# 3_CPLD.net
KiCad netlist of a schematic drawn in Altium Designer
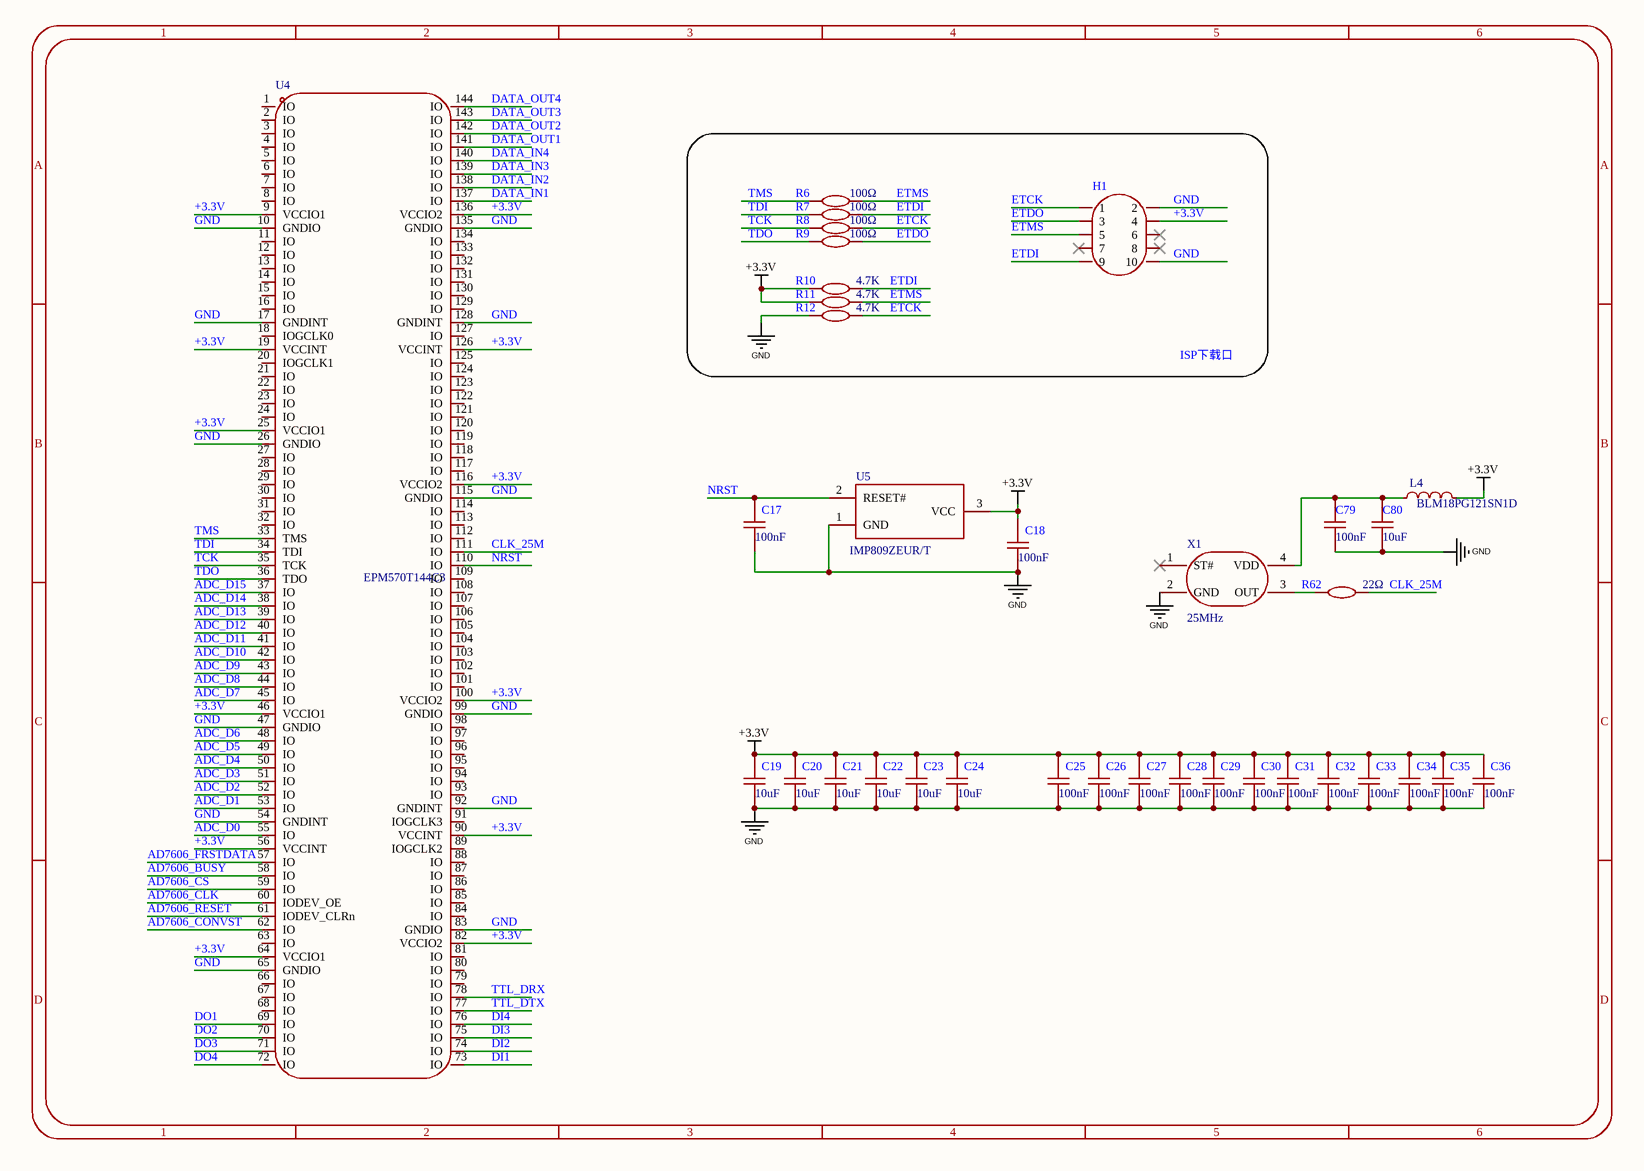
[diagram p0: 3_CPLD.schdoc]

(export (version "E")
  (design (tool "Eeschema 10.0.6"))
  (components
    (comp (ref "C17") (value "100nF") (footprint "C0603") (libsource (lib "34567890") (part "CAP_0603")))
    (comp (ref "C18") (value "100nF") (footprint "C0603") (libsource (lib "34567890") (part "CAP_0603")))
    (comp (ref "C19") (value "10uF") (footprint "C0805") (libsource (lib "34567890") (part "CAP_0805")))
    (comp (ref "C20") (value "10uF") (footprint "C0805") (libsource (lib "34567890") (part "CAP_0805")))
    (comp (ref "C21") (value "10uF") (footprint "C0805") (libsource (lib "34567890") (part "CAP_0805")))
    (comp (ref "C22") (value "10uF") (footprint "C0805") (libsource (lib "34567890") (part "CAP_0805")))
    (comp (ref "C23") (value "10uF") (footprint "C0805") (libsource (lib "34567890") (part "CAP_0805")))
    (comp (ref "C24") (value "10uF") (footprint "C0805") (libsource (lib "34567890") (part "CAP_0805")))
    (comp (ref "C25") (value "100nF") (footprint "C0603") (libsource (lib "34567890") (part "CAP_0603")))
    (comp (ref "C26") (value "100nF") (footprint "C0603") (libsource (lib "34567890") (part "CAP_0603")))
    (comp (ref "C27") (value "100nF") (footprint "C0603") (libsource (lib "34567890") (part "CAP_0603")))
    (comp (ref "C28") (value "100nF") (footprint "C0603") (libsource (lib "34567890") (part "CAP_0603")))
    (comp (ref "C29") (value "100nF") (footprint "C0603") (libsource (lib "34567890") (part "CAP_0603")))
    (comp (ref "C30") (value "100nF") (footprint "C0603") (libsource (lib "34567890") (part "CAP_0603")))
    (comp (ref "C31") (value "100nF") (footprint "C0603") (libsource (lib "34567890") (part "CAP_0603")))
    (comp (ref "C32") (value "100nF") (footprint "C0603") (libsource (lib "34567890") (part "CAP_0603")))
    (comp (ref "C33") (value "100nF") (footprint "C0603") (libsource (lib "34567890") (part "CAP_0603")))
    (comp (ref "C34") (value "100nF") (footprint "C0603") (libsource (lib "34567890") (part "CAP_0603")))
    (comp (ref "C35") (value "100nF") (footprint "C0603") (libsource (lib "34567890") (part "CAP_0603")))
    (comp (ref "C36") (value "100nF") (footprint "C0603") (libsource (lib "34567890") (part "CAP_0603")))
    (comp (ref "C79") (value "100nF") (footprint "C0603") (libsource (lib "34567890") (part "CAP_0603")))
    (comp (ref "C80") (value "10uF") (footprint "C0805") (libsource (lib "34567890") (part "CAP_0805")))
    (comp (ref "H1")
      (value "~")
      (footprint "HDR-TH_10P-P2.54-V-F-R2-C5-S2.54")
      (libsource (lib "34567890") (part "HDR-F_2.54_2x5"))
    )
    (comp (ref "L4")
      (value "BLM18PG121SN1D")
      (footprint "L0603")
      (libsource (lib "34567890") (part "BLM18PG121SN1D"))
    )
    (comp (ref "R6") (value "100Ω") (footprint "R0603") (libsource (lib "34567890") (part "Res_0603")))
    (comp (ref "R7") (value "100Ω") (footprint "R0603") (libsource (lib "34567890") (part "Res_0603")))
    (comp (ref "R8") (value "100Ω") (footprint "R0603") (libsource (lib "34567890") (part "Res_0603")))
    (comp (ref "R9") (value "100Ω") (footprint "R0603") (libsource (lib "34567890") (part "Res_0603")))
    (comp (ref "R10") (value "4.7K") (footprint "R0603") (libsource (lib "34567890") (part "Res_0603")))
    (comp (ref "R11") (value "4.7K") (footprint "R0603") (libsource (lib "34567890") (part "Res_0603")))
    (comp (ref "R12") (value "4.7K") (footprint "R0603") (libsource (lib "34567890") (part "Res_0603")))
    (comp (ref "R62") (value "22Ω") (footprint "R0603") (libsource (lib "34567890") (part "Res_0603")))
    (comp (ref "U4")
      (value "EPM570T144C3")
      (footprint "TQFP-144_L20.0-W20.0-P0.50-LS22.0-BL")
      (libsource (lib "34567890") (part "EPM570T144C3"))
    )
    (comp (ref "U5")
      (value "IMP809ZEUR/T")
      (footprint "SOT-23-3_L2.9-W1.6-P1.90-LS2.8-BR")
      (libsource (lib "34567890") (part "IMP809ZEUR/T"))
    )
    (comp (ref "X1")
      (value "25MHz")
      (footprint "OSC-SMD_4P-L2.5-W2.0-BL")
      (libsource (lib "34567890") (part "X1G0041710033"))
    )
  )
  (nets
    (net (code "1") (name "+3.3V") (class "Default")
      (node (ref "C18") (pin "2") (pinfunction "2_2") (pintype "passive"))
      (node (ref "C19") (pin "2") (pinfunction "2_2") (pintype "passive"))
      (node (ref "C20") (pin "2") (pinfunction "2_2") (pintype "passive"))
      (node (ref "C21") (pin "2") (pinfunction "2_2") (pintype "passive"))
      (node (ref "C22") (pin "2") (pinfunction "2_2") (pintype "passive"))
      (node (ref "C23") (pin "2") (pinfunction "2_2") (pintype "passive"))
      (node (ref "C24") (pin "2") (pinfunction "2_2") (pintype "passive"))
      (node (ref "C25") (pin "2") (pinfunction "2_2") (pintype "passive"))
      (node (ref "C26") (pin "2") (pinfunction "2_2") (pintype "passive"))
      (node (ref "C27") (pin "2") (pinfunction "2_2") (pintype "passive"))
      (node (ref "C28") (pin "2") (pinfunction "2_2") (pintype "passive"))
      (node (ref "C29") (pin "2") (pinfunction "2_2") (pintype "passive"))
      (node (ref "C30") (pin "2") (pinfunction "2_2") (pintype "passive"))
      (node (ref "C31") (pin "2") (pinfunction "2_2") (pintype "passive"))
      (node (ref "C32") (pin "2") (pinfunction "2_2") (pintype "passive"))
      (node (ref "C33") (pin "2") (pinfunction "2_2") (pintype "passive"))
      (node (ref "C34") (pin "2") (pinfunction "2_2") (pintype "passive"))
      (node (ref "C35") (pin "2") (pinfunction "2_2") (pintype "passive"))
      (node (ref "C36") (pin "2") (pinfunction "2_2") (pintype "passive"))
      (node (ref "H1") (pin "4") (pinfunction "4_4") (pintype "passive"))
      (node (ref "L4") (pin "2") (pinfunction "2_2") (pintype "passive"))
      (node (ref "R10") (pin "1") (pinfunction "1_1") (pintype "passive"))
      (node (ref "R11") (pin "1") (pinfunction "1_1") (pintype "passive"))
      (node (ref "U4") (pin "100") (pinfunction "VCCIO2_100") (pintype "passive"))
      (node (ref "U4") (pin "116") (pinfunction "VCCIO2_116") (pintype "passive"))
      (node (ref "U4") (pin "126") (pinfunction "VCCINT_126") (pintype "passive"))
      (node (ref "U4") (pin "136") (pinfunction "VCCIO2_136") (pintype "passive"))
      (node (ref "U4") (pin "19") (pinfunction "VCCINT_19") (pintype "passive"))
      (node (ref "U4") (pin "25") (pinfunction "VCCIO1_25") (pintype "passive"))
      (node (ref "U4") (pin "46") (pinfunction "VCCIO1_46") (pintype "passive"))
      (node (ref "U4") (pin "56") (pinfunction "VCCINT_56") (pintype "passive"))
      (node (ref "U4") (pin "64") (pinfunction "VCCIO1_64") (pintype "passive"))
      (node (ref "U4") (pin "82") (pinfunction "VCCIO2_82") (pintype "passive"))
      (node (ref "U4") (pin "9") (pinfunction "VCCIO1_9") (pintype "passive"))
      (node (ref "U4") (pin "90") (pinfunction "VCCINT_90") (pintype "passive"))
      (node (ref "U5") (pin "3") (pinfunction "VCC_3") (pintype "passive"))
    )
    (net (code "2") (name "/AD7606_BUSY") (class "Default")
      (node (ref "U4") (pin "58") (pinfunction "IO_58") (pintype "passive"))
    )
    (net (code "3") (name "/AD7606_CLK") (class "Default")
      (node (ref "U4") (pin "60") (pinfunction "IODEV_OE_60") (pintype "passive"))
    )
    (net (code "4") (name "/AD7606_CONVST") (class "Default")
      (node (ref "U4") (pin "62") (pinfunction "IO_62") (pintype "passive"))
    )
    (net (code "5") (name "/AD7606_CS") (class "Default")
      (node (ref "U4") (pin "59") (pinfunction "IO_59") (pintype "passive"))
    )
    (net (code "6") (name "/AD7606_FRSTDATA") (class "Default")
      (node (ref "U4") (pin "57") (pinfunction "IO_57") (pintype "passive"))
    )
    (net (code "7") (name "/AD7606_RESET") (class "Default")
      (node (ref "U4") (pin "61") (pinfunction "IODEV_CLRn_61") (pintype "passive"))
    )
    (net (code "8") (name "/ADC_D0") (class "Default")
      (node (ref "U4") (pin "55") (pinfunction "IO_55") (pintype "passive"))
    )
    (net (code "9") (name "/ADC_D1") (class "Default")
      (node (ref "U4") (pin "53") (pinfunction "IO_53") (pintype "passive"))
    )
    (net (code "10") (name "/ADC_D2") (class "Default")
      (node (ref "U4") (pin "52") (pinfunction "IO_52") (pintype "passive"))
    )
    (net (code "11") (name "/ADC_D3") (class "Default")
      (node (ref "U4") (pin "51") (pinfunction "IO_51") (pintype "passive"))
    )
    (net (code "12") (name "/ADC_D4") (class "Default")
      (node (ref "U4") (pin "50") (pinfunction "IO_50") (pintype "passive"))
    )
    (net (code "13") (name "/ADC_D5") (class "Default")
      (node (ref "U4") (pin "49") (pinfunction "IO_49") (pintype "passive"))
    )
    (net (code "14") (name "/ADC_D6") (class "Default")
      (node (ref "U4") (pin "48") (pinfunction "IO_48") (pintype "passive"))
    )
    (net (code "15") (name "/ADC_D7") (class "Default")
      (node (ref "U4") (pin "45") (pinfunction "IO_45") (pintype "passive"))
    )
    (net (code "16") (name "/ADC_D8") (class "Default")
      (node (ref "U4") (pin "44") (pinfunction "IO_44") (pintype "passive"))
    )
    (net (code "17") (name "/ADC_D9") (class "Default")
      (node (ref "U4") (pin "43") (pinfunction "IO_43") (pintype "passive"))
    )
    (net (code "18") (name "/ADC_D10") (class "Default")
      (node (ref "U4") (pin "42") (pinfunction "IO_42") (pintype "passive"))
    )
    (net (code "19") (name "/ADC_D11") (class "Default")
      (node (ref "U4") (pin "41") (pinfunction "IO_41") (pintype "passive"))
    )
    (net (code "20") (name "/ADC_D12") (class "Default")
      (node (ref "U4") (pin "40") (pinfunction "IO_40") (pintype "passive"))
    )
    (net (code "21") (name "/ADC_D13") (class "Default")
      (node (ref "U4") (pin "39") (pinfunction "IO_39") (pintype "passive"))
    )
    (net (code "22") (name "/ADC_D14") (class "Default")
      (node (ref "U4") (pin "38") (pinfunction "IO_38") (pintype "passive"))
    )
    (net (code "23") (name "/ADC_D15") (class "Default")
      (node (ref "U4") (pin "37") (pinfunction "IO_37") (pintype "passive"))
    )
    (net (code "24") (name "/CLK_25M") (class "Default")
      (node (ref "R62") (pin "2") (pinfunction "2_2") (pintype "passive"))
      (node (ref "U4") (pin "111") (pinfunction "IO_111") (pintype "passive"))
    )
    (net (code "25") (name "/DATA_IN1") (class "Default")
      (node (ref "U4") (pin "137") (pinfunction "IO_137") (pintype "passive"))
    )
    (net (code "26") (name "/DATA_IN2") (class "Default")
      (node (ref "U4") (pin "138") (pinfunction "IO_138") (pintype "passive"))
    )
    (net (code "27") (name "/DATA_IN3") (class "Default")
      (node (ref "U4") (pin "139") (pinfunction "IO_139") (pintype "passive"))
    )
    (net (code "28") (name "/DATA_IN4") (class "Default")
      (node (ref "U4") (pin "140") (pinfunction "IO_140") (pintype "passive"))
    )
    (net (code "29") (name "/DATA_OUT1") (class "Default")
      (node (ref "U4") (pin "141") (pinfunction "IO_141") (pintype "passive"))
    )
    (net (code "30") (name "/DATA_OUT2") (class "Default")
      (node (ref "U4") (pin "142") (pinfunction "IO_142") (pintype "passive"))
    )
    (net (code "31") (name "/DATA_OUT3") (class "Default")
      (node (ref "U4") (pin "143") (pinfunction "IO_143") (pintype "passive"))
    )
    (net (code "32") (name "/DATA_OUT4") (class "Default")
      (node (ref "U4") (pin "144") (pinfunction "IO_144") (pintype "passive"))
    )
    (net (code "33") (name "/DI1") (class "Default")
      (node (ref "U4") (pin "73") (pinfunction "IO_73") (pintype "passive"))
    )
    (net (code "34") (name "/DI2") (class "Default")
      (node (ref "U4") (pin "74") (pinfunction "IO_74") (pintype "passive"))
    )
    (net (code "35") (name "/DI3") (class "Default")
      (node (ref "U4") (pin "75") (pinfunction "IO_75") (pintype "passive"))
    )
    (net (code "36") (name "/DI4") (class "Default")
      (node (ref "U4") (pin "76") (pinfunction "IO_76") (pintype "passive"))
    )
    (net (code "37") (name "/DO1") (class "Default")
      (node (ref "U4") (pin "69") (pinfunction "IO_69") (pintype "passive"))
    )
    (net (code "38") (name "/DO2") (class "Default")
      (node (ref "U4") (pin "70") (pinfunction "IO_70") (pintype "passive"))
    )
    (net (code "39") (name "/DO3") (class "Default")
      (node (ref "U4") (pin "71") (pinfunction "IO_71") (pintype "passive"))
    )
    (net (code "40") (name "/DO4") (class "Default")
      (node (ref "U4") (pin "72") (pinfunction "IO_72") (pintype "passive"))
    )
    (net (code "41") (name "/ETCK") (class "Default")
      (node (ref "H1") (pin "1") (pinfunction "1_1") (pintype "passive"))
      (node (ref "R12") (pin "2") (pinfunction "2_2") (pintype "passive"))
      (node (ref "R8") (pin "2") (pinfunction "2_2") (pintype "passive"))
    )
    (net (code "42") (name "/ETDI") (class "Default")
      (node (ref "H1") (pin "9") (pinfunction "9_9") (pintype "passive"))
      (node (ref "R10") (pin "2") (pinfunction "2_2") (pintype "passive"))
      (node (ref "R7") (pin "2") (pinfunction "2_2") (pintype "passive"))
    )
    (net (code "43") (name "/ETDO") (class "Default")
      (node (ref "H1") (pin "3") (pinfunction "3_3") (pintype "passive"))
      (node (ref "R9") (pin "2") (pinfunction "2_2") (pintype "passive"))
    )
    (net (code "44") (name "/ETMS") (class "Default")
      (node (ref "H1") (pin "5") (pinfunction "5_5") (pintype "passive"))
      (node (ref "R11") (pin "2") (pinfunction "2_2") (pintype "passive"))
      (node (ref "R6") (pin "2") (pinfunction "2_2") (pintype "passive"))
    )
    (net (code "45") (name "/NRST") (class "Default")
      (node (ref "C17") (pin "2") (pinfunction "2_2") (pintype "passive"))
      (node (ref "U4") (pin "110") (pinfunction "IO_110") (pintype "passive"))
      (node (ref "U5") (pin "2") (pinfunction "RESET#_2") (pintype "passive"))
    )
    (net (code "46") (name "/TCK") (class "Default")
      (node (ref "R8") (pin "1") (pinfunction "1_1") (pintype "passive"))
      (node (ref "U4") (pin "35") (pinfunction "TCK_35") (pintype "passive"))
    )
    (net (code "47") (name "/TDI") (class "Default")
      (node (ref "R7") (pin "1") (pinfunction "1_1") (pintype "passive"))
      (node (ref "U4") (pin "34") (pinfunction "TDI_34") (pintype "passive"))
    )
    (net (code "48") (name "/TDO") (class "Default")
      (node (ref "R9") (pin "1") (pinfunction "1_1") (pintype "passive"))
      (node (ref "U4") (pin "36") (pinfunction "TDO_36") (pintype "passive"))
    )
    (net (code "49") (name "/TMS") (class "Default")
      (node (ref "R6") (pin "1") (pinfunction "1_1") (pintype "passive"))
      (node (ref "U4") (pin "33") (pinfunction "TMS_33") (pintype "passive"))
    )
    (net (code "50") (name "/TTL_DRX") (class "Default")
      (node (ref "U4") (pin "78") (pinfunction "IO_78") (pintype "passive"))
    )
    (net (code "51") (name "/TTL_DTX") (class "Default")
      (node (ref "U4") (pin "77") (pinfunction "IO_77") (pintype "passive"))
    )
    (net (code "52") (name "GND") (class "Default")
      (node (ref "C17") (pin "1") (pinfunction "1_1") (pintype "passive"))
      (node (ref "C18") (pin "1") (pinfunction "1_1") (pintype "passive"))
      (node (ref "C19") (pin "1") (pinfunction "1_1") (pintype "passive"))
      (node (ref "C20") (pin "1") (pinfunction "1_1") (pintype "passive"))
      (node (ref "C21") (pin "1") (pinfunction "1_1") (pintype "passive"))
      (node (ref "C22") (pin "1") (pinfunction "1_1") (pintype "passive"))
      (node (ref "C23") (pin "1") (pinfunction "1_1") (pintype "passive"))
      (node (ref "C24") (pin "1") (pinfunction "1_1") (pintype "passive"))
      (node (ref "C25") (pin "1") (pinfunction "1_1") (pintype "passive"))
      (node (ref "C26") (pin "1") (pinfunction "1_1") (pintype "passive"))
      (node (ref "C27") (pin "1") (pinfunction "1_1") (pintype "passive"))
      (node (ref "C28") (pin "1") (pinfunction "1_1") (pintype "passive"))
      (node (ref "C29") (pin "1") (pinfunction "1_1") (pintype "passive"))
      (node (ref "C30") (pin "1") (pinfunction "1_1") (pintype "passive"))
      (node (ref "C31") (pin "1") (pinfunction "1_1") (pintype "passive"))
      (node (ref "C32") (pin "1") (pinfunction "1_1") (pintype "passive"))
      (node (ref "C33") (pin "1") (pinfunction "1_1") (pintype "passive"))
      (node (ref "C34") (pin "1") (pinfunction "1_1") (pintype "passive"))
      (node (ref "C35") (pin "1") (pinfunction "1_1") (pintype "passive"))
      (node (ref "C36") (pin "1") (pinfunction "1_1") (pintype "passive"))
      (node (ref "C79") (pin "2") (pinfunction "2_2") (pintype "passive"))
      (node (ref "C80") (pin "1") (pinfunction "1_1") (pintype "passive"))
      (node (ref "H1") (pin "10") (pinfunction "10_10") (pintype "passive"))
      (node (ref "H1") (pin "2") (pinfunction "2_2") (pintype "passive"))
      (node (ref "R12") (pin "1") (pinfunction "1_1") (pintype "passive"))
      (node (ref "U4") (pin "10") (pinfunction "GNDIO_10") (pintype "passive"))
      (node (ref "U4") (pin "115") (pinfunction "GNDIO_115") (pintype "passive"))
      (node (ref "U4") (pin "128") (pinfunction "GNDINT_128") (pintype "passive"))
      (node (ref "U4") (pin "135") (pinfunction "GNDIO_135") (pintype "passive"))
      (node (ref "U4") (pin "17") (pinfunction "GNDINT_17") (pintype "passive"))
      (node (ref "U4") (pin "26") (pinfunction "GNDIO_26") (pintype "passive"))
      (node (ref "U4") (pin "47") (pinfunction "GNDIO_47") (pintype "passive"))
      (node (ref "U4") (pin "54") (pinfunction "GNDINT_54") (pintype "passive"))
      (node (ref "U4") (pin "65") (pinfunction "GNDIO_65") (pintype "passive"))
      (node (ref "U4") (pin "83") (pinfunction "GNDIO_83") (pintype "passive"))
      (node (ref "U4") (pin "92") (pinfunction "GNDINT_92") (pintype "passive"))
      (node (ref "U4") (pin "99") (pinfunction "GNDIO_99") (pintype "passive"))
      (node (ref "U5") (pin "1") (pinfunction "GND_1") (pintype "passive"))
      (node (ref "X1") (pin "2") (pinfunction "GND_2") (pintype "passive"))
    )
    (net (code "53") (name "Net-(X1-OUT)") (class "Default")
      (node (ref "R62") (pin "1") (pinfunction "1_1") (pintype "passive"))
      (node (ref "X1") (pin "3") (pinfunction "OUT_3") (pintype "passive"))
    )
    (net (code "54") (name "Net-(X1-VDD)") (class "Default")
      (node (ref "C79") (pin "1") (pinfunction "1_1") (pintype "passive"))
      (node (ref "C80") (pin "2") (pinfunction "2_2") (pintype "passive"))
      (node (ref "L4") (pin "1") (pinfunction "1_1") (pintype "passive"))
      (node (ref "X1") (pin "4") (pinfunction "VDD_4") (pintype "passive"))
    )
    (net (code "55") (name "unconnected-(H1-Pad6)") (class "Default")
      (node (ref "H1") (pin "6") (pinfunction "6_6") (pintype "passive+no_connect"))
    )
    (net (code "56") (name "unconnected-(H1-Pad7)") (class "Default")
      (node (ref "H1") (pin "7") (pinfunction "7_7") (pintype "passive+no_connect"))
    )
    (net (code "57") (name "unconnected-(H1-Pad8)") (class "Default")
      (node (ref "H1") (pin "8") (pinfunction "8_8") (pintype "passive+no_connect"))
    )
    (net (code "58") (name "unconnected-(U4-IO-Pad1)") (class "Default")
      (node (ref "U4") (pin "1") (pinfunction "IO_1") (pintype "passive"))
    )
    (net (code "59") (name "unconnected-(U4-IO-Pad2)") (class "Default")
      (node (ref "U4") (pin "2") (pinfunction "IO_2") (pintype "passive"))
    )
    (net (code "60") (name "unconnected-(U4-IO-Pad3)") (class "Default")
      (node (ref "U4") (pin "3") (pinfunction "IO_3") (pintype "passive"))
    )
    (net (code "61") (name "unconnected-(U4-IO-Pad4)") (class "Default")
      (node (ref "U4") (pin "4") (pinfunction "IO_4") (pintype "passive"))
    )
    (net (code "62") (name "unconnected-(U4-IO-Pad5)") (class "Default")
      (node (ref "U4") (pin "5") (pinfunction "IO_5") (pintype "passive"))
    )
    (net (code "63") (name "unconnected-(U4-IO-Pad6)") (class "Default")
      (node (ref "U4") (pin "6") (pinfunction "IO_6") (pintype "passive"))
    )
    (net (code "64") (name "unconnected-(U4-IO-Pad7)") (class "Default")
      (node (ref "U4") (pin "7") (pinfunction "IO_7") (pintype "passive"))
    )
    (net (code "65") (name "unconnected-(U4-IO-Pad8)") (class "Default")
      (node (ref "U4") (pin "8") (pinfunction "IO_8") (pintype "passive"))
    )
    (net (code "66") (name "unconnected-(U4-IO-Pad11)") (class "Default")
      (node (ref "U4") (pin "11") (pinfunction "IO_11") (pintype "passive"))
    )
    (net (code "67") (name "unconnected-(U4-IO-Pad12)") (class "Default")
      (node (ref "U4") (pin "12") (pinfunction "IO_12") (pintype "passive"))
    )
    (net (code "68") (name "unconnected-(U4-IO-Pad13)") (class "Default")
      (node (ref "U4") (pin "13") (pinfunction "IO_13") (pintype "passive"))
    )
    (net (code "69") (name "unconnected-(U4-IO-Pad14)") (class "Default")
      (node (ref "U4") (pin "14") (pinfunction "IO_14") (pintype "passive"))
    )
    (net (code "70") (name "unconnected-(U4-IO-Pad15)") (class "Default")
      (node (ref "U4") (pin "15") (pinfunction "IO_15") (pintype "passive"))
    )
    (net (code "71") (name "unconnected-(U4-IO-Pad16)") (class "Default")
      (node (ref "U4") (pin "16") (pinfunction "IO_16") (pintype "passive"))
    )
    (net (code "72") (name "unconnected-(U4-IO-Pad21)") (class "Default")
      (node (ref "U4") (pin "21") (pinfunction "IO_21") (pintype "passive"))
    )
    (net (code "73") (name "unconnected-(U4-IO-Pad22)") (class "Default")
      (node (ref "U4") (pin "22") (pinfunction "IO_22") (pintype "passive"))
    )
    (net (code "74") (name "unconnected-(U4-IO-Pad23)") (class "Default")
      (node (ref "U4") (pin "23") (pinfunction "IO_23") (pintype "passive"))
    )
    (net (code "75") (name "unconnected-(U4-IO-Pad24)") (class "Default")
      (node (ref "U4") (pin "24") (pinfunction "IO_24") (pintype "passive"))
    )
    (net (code "76") (name "unconnected-(U4-IO-Pad27)") (class "Default")
      (node (ref "U4") (pin "27") (pinfunction "IO_27") (pintype "passive"))
    )
    (net (code "77") (name "unconnected-(U4-IO-Pad28)") (class "Default")
      (node (ref "U4") (pin "28") (pinfunction "IO_28") (pintype "passive"))
    )
    (net (code "78") (name "unconnected-(U4-IO-Pad29)") (class "Default")
      (node (ref "U4") (pin "29") (pinfunction "IO_29") (pintype "passive"))
    )
    (net (code "79") (name "unconnected-(U4-IO-Pad30)") (class "Default")
      (node (ref "U4") (pin "30") (pinfunction "IO_30") (pintype "passive"))
    )
    (net (code "80") (name "unconnected-(U4-IO-Pad31)") (class "Default")
      (node (ref "U4") (pin "31") (pinfunction "IO_31") (pintype "passive"))
    )
    (net (code "81") (name "unconnected-(U4-IO-Pad32)") (class "Default")
      (node (ref "U4") (pin "32") (pinfunction "IO_32") (pintype "passive"))
    )
    (net (code "82") (name "unconnected-(U4-IO-Pad63)") (class "Default")
      (node (ref "U4") (pin "63") (pinfunction "IO_63") (pintype "passive"))
    )
    (net (code "83") (name "unconnected-(U4-IO-Pad66)") (class "Default")
      (node (ref "U4") (pin "66") (pinfunction "IO_66") (pintype "passive"))
    )
    (net (code "84") (name "unconnected-(U4-IO-Pad67)") (class "Default")
      (node (ref "U4") (pin "67") (pinfunction "IO_67") (pintype "passive"))
    )
    (net (code "85") (name "unconnected-(U4-IO-Pad68)") (class "Default")
      (node (ref "U4") (pin "68") (pinfunction "IO_68") (pintype "passive"))
    )
    (net (code "86") (name "unconnected-(U4-IO-Pad79)") (class "Default")
      (node (ref "U4") (pin "79") (pinfunction "IO_79") (pintype "passive"))
    )
    (net (code "87") (name "unconnected-(U4-IO-Pad80)") (class "Default")
      (node (ref "U4") (pin "80") (pinfunction "IO_80") (pintype "passive"))
    )
    (net (code "88") (name "unconnected-(U4-IO-Pad81)") (class "Default")
      (node (ref "U4") (pin "81") (pinfunction "IO_81") (pintype "passive"))
    )
    (net (code "89") (name "unconnected-(U4-IO-Pad84)") (class "Default")
      (node (ref "U4") (pin "84") (pinfunction "IO_84") (pintype "passive"))
    )
    (net (code "90") (name "unconnected-(U4-IO-Pad85)") (class "Default")
      (node (ref "U4") (pin "85") (pinfunction "IO_85") (pintype "passive"))
    )
    (net (code "91") (name "unconnected-(U4-IO-Pad86)") (class "Default")
      (node (ref "U4") (pin "86") (pinfunction "IO_86") (pintype "passive"))
    )
    (net (code "92") (name "unconnected-(U4-IO-Pad87)") (class "Default")
      (node (ref "U4") (pin "87") (pinfunction "IO_87") (pintype "passive"))
    )
    (net (code "93") (name "unconnected-(U4-IO-Pad88)") (class "Default")
      (node (ref "U4") (pin "88") (pinfunction "IO_88") (pintype "passive"))
    )
    (net (code "94") (name "unconnected-(U4-IO-Pad93)") (class "Default")
      (node (ref "U4") (pin "93") (pinfunction "IO_93") (pintype "passive"))
    )
    (net (code "95") (name "unconnected-(U4-IO-Pad94)") (class "Default")
      (node (ref "U4") (pin "94") (pinfunction "IO_94") (pintype "passive"))
    )
    (net (code "96") (name "unconnected-(U4-IO-Pad95)") (class "Default")
      (node (ref "U4") (pin "95") (pinfunction "IO_95") (pintype "passive"))
    )
    (net (code "97") (name "unconnected-(U4-IO-Pad96)") (class "Default")
      (node (ref "U4") (pin "96") (pinfunction "IO_96") (pintype "passive"))
    )
    (net (code "98") (name "unconnected-(U4-IO-Pad97)") (class "Default")
      (node (ref "U4") (pin "97") (pinfunction "IO_97") (pintype "passive"))
    )
    (net (code "99") (name "unconnected-(U4-IO-Pad98)") (class "Default")
      (node (ref "U4") (pin "98") (pinfunction "IO_98") (pintype "passive"))
    )
    (net (code "100") (name "unconnected-(U4-IO-Pad101)") (class "Default")
      (node (ref "U4") (pin "101") (pinfunction "IO_101") (pintype "passive"))
    )
    (net (code "101") (name "unconnected-(U4-IO-Pad102)") (class "Default")
      (node (ref "U4") (pin "102") (pinfunction "IO_102") (pintype "passive"))
    )
    (net (code "102") (name "unconnected-(U4-IO-Pad103)") (class "Default")
      (node (ref "U4") (pin "103") (pinfunction "IO_103") (pintype "passive"))
    )
    (net (code "103") (name "unconnected-(U4-IO-Pad104)") (class "Default")
      (node (ref "U4") (pin "104") (pinfunction "IO_104") (pintype "passive"))
    )
    (net (code "104") (name "unconnected-(U4-IO-Pad105)") (class "Default")
      (node (ref "U4") (pin "105") (pinfunction "IO_105") (pintype "passive"))
    )
    (net (code "105") (name "unconnected-(U4-IO-Pad106)") (class "Default")
      (node (ref "U4") (pin "106") (pinfunction "IO_106") (pintype "passive"))
    )
    (net (code "106") (name "unconnected-(U4-IO-Pad107)") (class "Default")
      (node (ref "U4") (pin "107") (pinfunction "IO_107") (pintype "passive"))
    )
    (net (code "107") (name "unconnected-(U4-IO-Pad108)") (class "Default")
      (node (ref "U4") (pin "108") (pinfunction "IO_108") (pintype "passive"))
    )
    (net (code "108") (name "unconnected-(U4-IO-Pad109)") (class "Default")
      (node (ref "U4") (pin "109") (pinfunction "IO_109") (pintype "passive"))
    )
    (net (code "109") (name "unconnected-(U4-IO-Pad112)") (class "Default")
      (node (ref "U4") (pin "112") (pinfunction "IO_112") (pintype "passive"))
    )
    (net (code "110") (name "unconnected-(U4-IO-Pad113)") (class "Default")
      (node (ref "U4") (pin "113") (pinfunction "IO_113") (pintype "passive"))
    )
    (net (code "111") (name "unconnected-(U4-IO-Pad114)") (class "Default")
      (node (ref "U4") (pin "114") (pinfunction "IO_114") (pintype "passive"))
    )
    (net (code "112") (name "unconnected-(U4-IO-Pad117)") (class "Default")
      (node (ref "U4") (pin "117") (pinfunction "IO_117") (pintype "passive"))
    )
    (net (code "113") (name "unconnected-(U4-IO-Pad118)") (class "Default")
      (node (ref "U4") (pin "118") (pinfunction "IO_118") (pintype "passive"))
    )
    (net (code "114") (name "unconnected-(U4-IO-Pad119)") (class "Default")
      (node (ref "U4") (pin "119") (pinfunction "IO_119") (pintype "passive"))
    )
    (net (code "115") (name "unconnected-(U4-IO-Pad120)") (class "Default")
      (node (ref "U4") (pin "120") (pinfunction "IO_120") (pintype "passive"))
    )
    (net (code "116") (name "unconnected-(U4-IO-Pad121)") (class "Default")
      (node (ref "U4") (pin "121") (pinfunction "IO_121") (pintype "passive"))
    )
    (net (code "117") (name "unconnected-(U4-IO-Pad122)") (class "Default")
      (node (ref "U4") (pin "122") (pinfunction "IO_122") (pintype "passive"))
    )
    (net (code "118") (name "unconnected-(U4-IO-Pad123)") (class "Default")
      (node (ref "U4") (pin "123") (pinfunction "IO_123") (pintype "passive"))
    )
    (net (code "119") (name "unconnected-(U4-IO-Pad124)") (class "Default")
      (node (ref "U4") (pin "124") (pinfunction "IO_124") (pintype "passive"))
    )
    (net (code "120") (name "unconnected-(U4-IO-Pad125)") (class "Default")
      (node (ref "U4") (pin "125") (pinfunction "IO_125") (pintype "passive"))
    )
    (net (code "121") (name "unconnected-(U4-IO-Pad127)") (class "Default")
      (node (ref "U4") (pin "127") (pinfunction "IO_127") (pintype "passive"))
    )
    (net (code "122") (name "unconnected-(U4-IO-Pad129)") (class "Default")
      (node (ref "U4") (pin "129") (pinfunction "IO_129") (pintype "passive"))
    )
    (net (code "123") (name "unconnected-(U4-IO-Pad130)") (class "Default")
      (node (ref "U4") (pin "130") (pinfunction "IO_130") (pintype "passive"))
    )
    (net (code "124") (name "unconnected-(U4-IO-Pad131)") (class "Default")
      (node (ref "U4") (pin "131") (pinfunction "IO_131") (pintype "passive"))
    )
    (net (code "125") (name "unconnected-(U4-IO-Pad132)") (class "Default")
      (node (ref "U4") (pin "132") (pinfunction "IO_132") (pintype "passive"))
    )
    (net (code "126") (name "unconnected-(U4-IO-Pad133)") (class "Default")
      (node (ref "U4") (pin "133") (pinfunction "IO_133") (pintype "passive"))
    )
    (net (code "127") (name "unconnected-(U4-IO-Pad134)") (class "Default")
      (node (ref "U4") (pin "134") (pinfunction "IO_134") (pintype "passive"))
    )
    (net (code "128") (name "unconnected-(U4-IOGCLK0-Pad18)") (class "Default")
      (node (ref "U4") (pin "18") (pinfunction "IOGCLK0_18") (pintype "passive"))
    )
    (net (code "129") (name "unconnected-(U4-IOGCLK1-Pad20)") (class "Default")
      (node (ref "U4") (pin "20") (pinfunction "IOGCLK1_20") (pintype "passive"))
    )
    (net (code "130") (name "unconnected-(U4-IOGCLK2-Pad89)") (class "Default")
      (node (ref "U4") (pin "89") (pinfunction "IOGCLK2_89") (pintype "passive"))
    )
    (net (code "131") (name "unconnected-(U4-IOGCLK3-Pad91)") (class "Default")
      (node (ref "U4") (pin "91") (pinfunction "IOGCLK3_91") (pintype "passive"))
    )
    (net (code "132") (name "unconnected-(X1-ST#-Pad1)") (class "Default")
      (node (ref "X1") (pin "1") (pinfunction "ST#_1") (pintype "passive+no_connect"))
    )
  )
)
